# Sheet1.net
KiCad netlist of a schematic drawn in Altium Designer
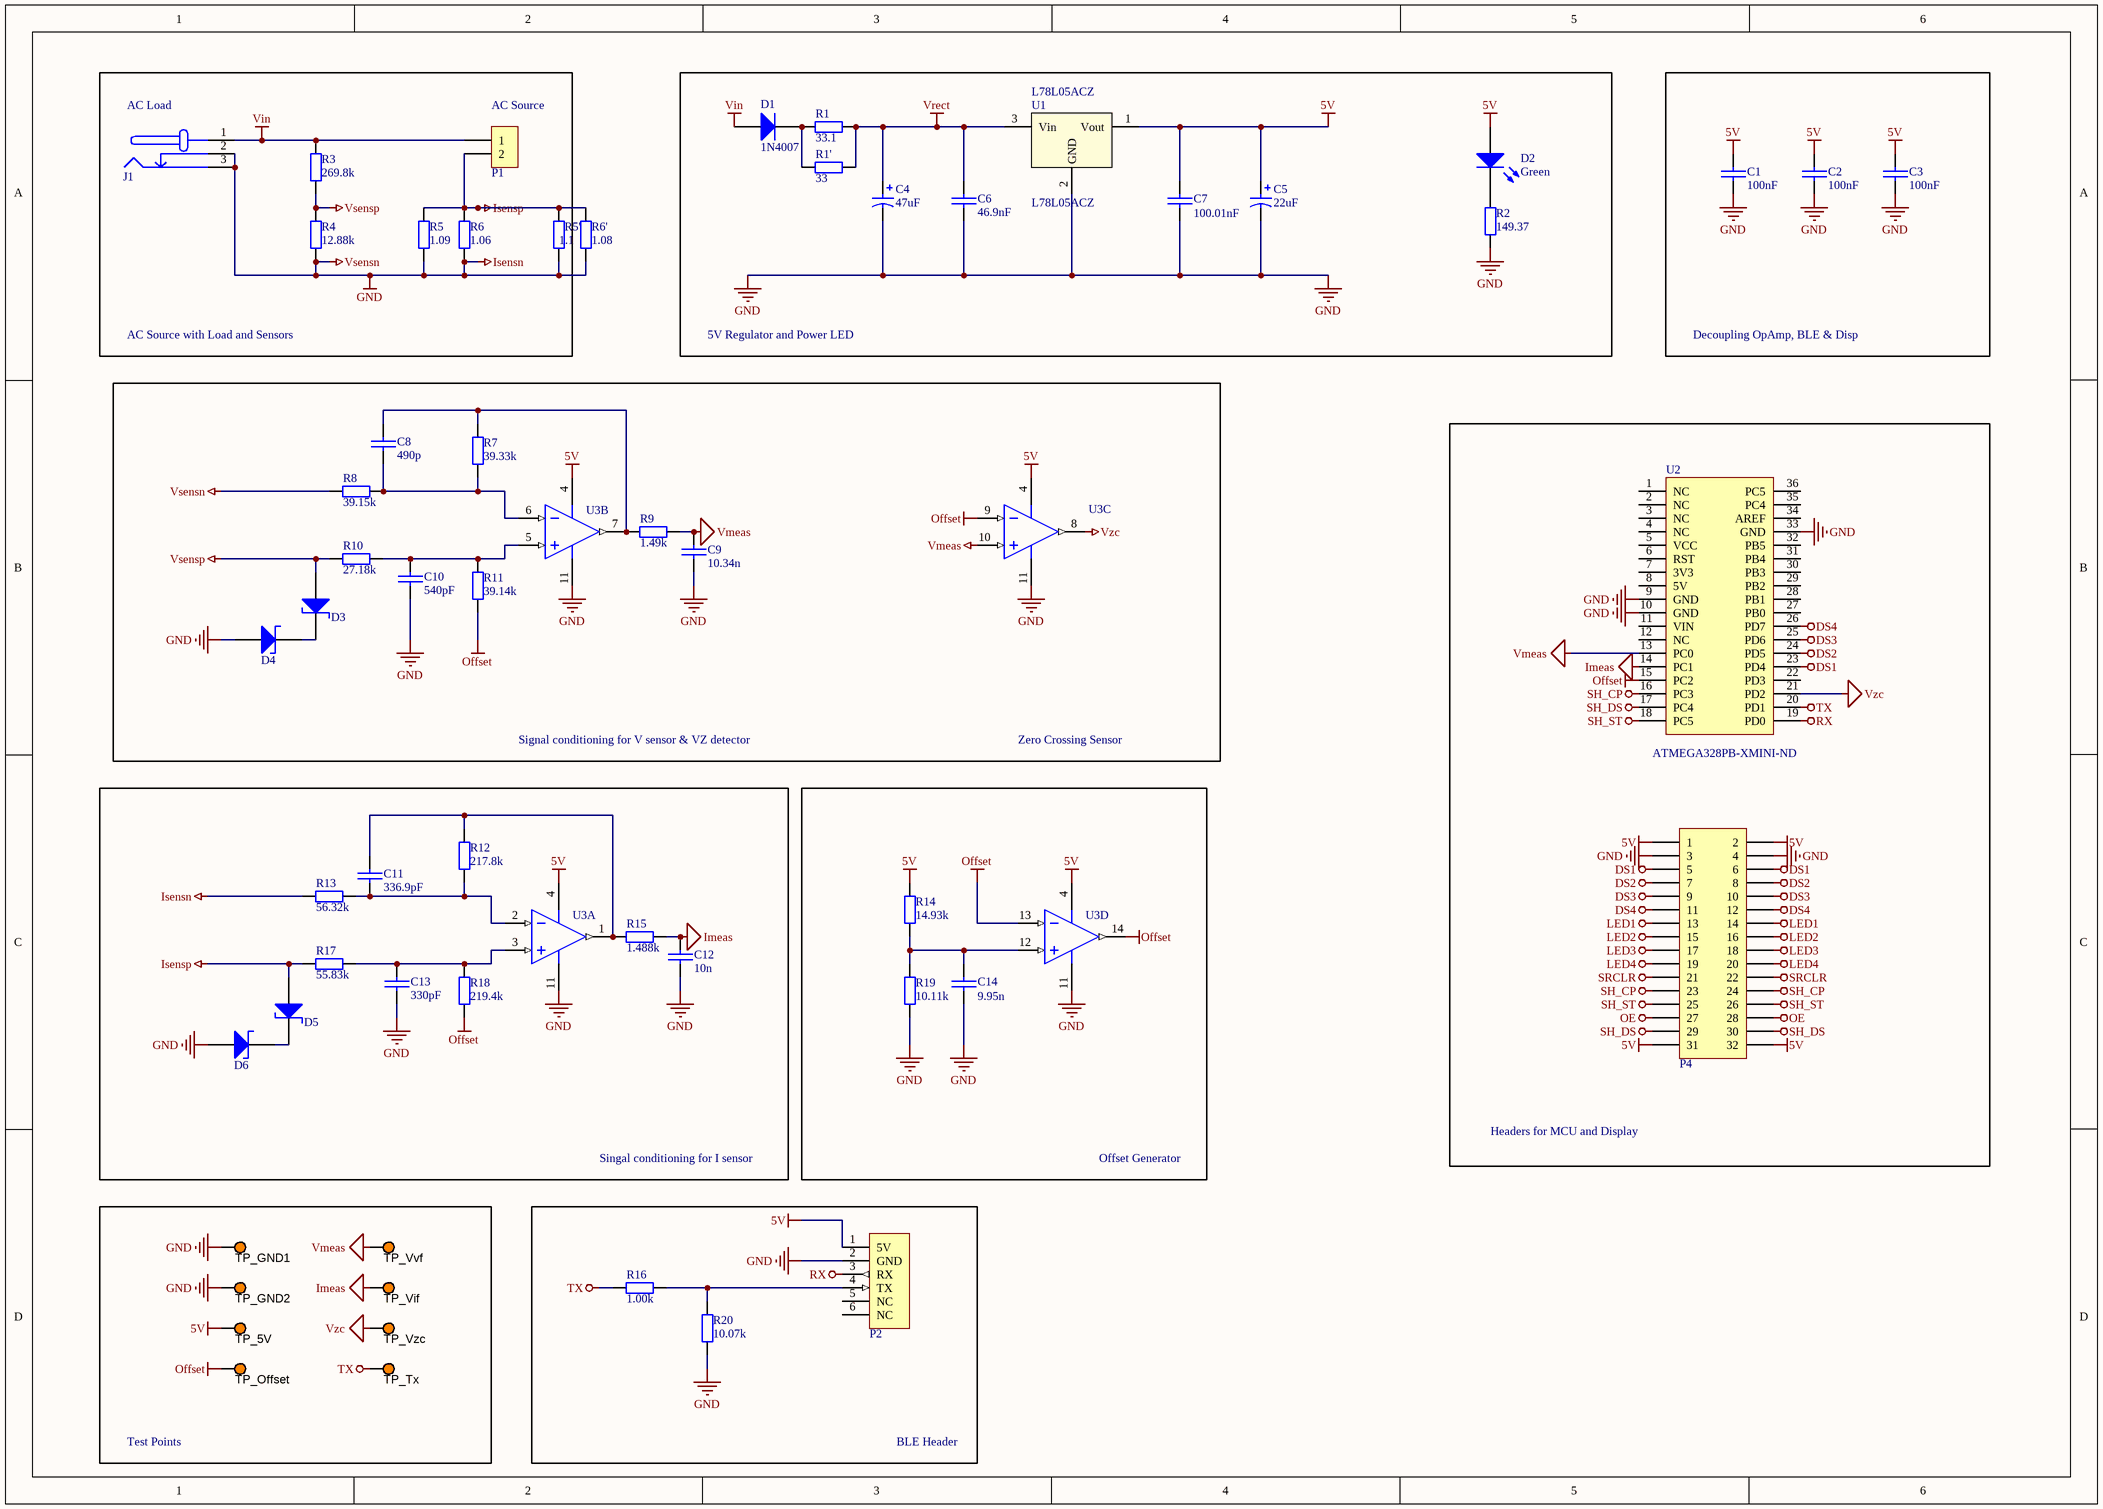
[diagram p0: Sheet1.SchDoc]

(export (version "E")
  (design (tool "Eeschema 10.0.6"))
  (components
    (comp (ref "C1")
      (value "100nF")
      (footprint "CCAP-5P0")
      (description "TH ceramic capacitor with 5mm pitch")
      (libsource (lib "EE209_Library") (part "CerCap_TH_5P0"))
    )
    (comp (ref "C2")
      (value "100nF")
      (footprint "CCAP-5P0")
      (description "TH ceramic capacitor with 5mm pitch")
      (libsource (lib "EE209_Library") (part "CerCap_TH_5P0"))
    )
    (comp (ref "C3")
      (value "100nF")
      (footprint "CCAP-5P0")
      (description "TH ceramic capacitor with 5mm pitch")
      (libsource (lib "EE209_Library") (part "CerCap_TH_5P0"))
    )
    (comp (ref "C4")
      (value "47uF")
      (footprint "CAP-RAD-2.5mm Pitch")
      (description "Electrolytic capacitor with radial package, 2mm pitch and 5.2mm diameter")
      (fields (field (name "PUBLISHER") "Altium Limited"))
      (libsource (lib "EE209_Library") (part "ElecCap_TH_2P0"))
    )
    (comp (ref "C5")
      (value "22uF")
      (footprint "CAP-RAD-2.5mm Pitch")
      (description "Electrolytic capacitor with radial package, 2mm pitch and 5.2mm diameter")
      (fields (field (name "PUBLISHER") "Altium Limited"))
      (libsource (lib "EE209_Library") (part "ElecCap_TH_2P0"))
    )
    (comp (ref "C6")
      (value "46.9nF")
      (footprint "CCAP-5P0")
      (description "TH ceramic capacitor with 5mm pitch")
      (libsource (lib "EE209_Library") (part "CerCap_TH_5P0"))
    )
    (comp (ref "C7")
      (value "100.01nF")
      (footprint "CCAP-5P0")
      (description "TH ceramic capacitor with 5mm pitch")
      (libsource (lib "EE209_Library") (part "CerCap_TH_5P0"))
    )
    (comp (ref "C8")
      (value "490p")
      (footprint "CCAP-5P0")
      (description "TH ceramic capacitor with 5mm pitch")
      (libsource (lib "EE209_Library") (part "CerCap_TH_5P0"))
    )
    (comp (ref "C9")
      (value "10.34n")
      (footprint "CCAP-5P0")
      (description "TH ceramic capacitor with 5mm pitch")
      (libsource (lib "EE209_Library") (part "CerCap_TH_5P0"))
    )
    (comp (ref "C10")
      (value "540pF")
      (footprint "CCAP-5P0")
      (description "TH ceramic capacitor with 5mm pitch")
      (libsource (lib "EE209_Library") (part "CerCap_TH_5P0"))
    )
    (comp (ref "C11")
      (value "336.9pF")
      (footprint "CCAP-5P0")
      (description "TH ceramic capacitor with 5mm pitch")
      (libsource (lib "EE209_Library") (part "CerCap_TH_5P0"))
    )
    (comp (ref "C12")
      (value "10n")
      (footprint "CCAP-5P0")
      (description "TH ceramic capacitor with 5mm pitch")
      (libsource (lib "EE209_Library") (part "CerCap_TH_5P0"))
    )
    (comp (ref "C13")
      (value "330pF")
      (footprint "CCAP-5P0")
      (description "TH ceramic capacitor with 5mm pitch")
      (libsource (lib "EE209_Library") (part "CerCap_TH_5P0"))
    )
    (comp (ref "C14")
      (value "9.95n")
      (footprint "CCAP-5P0")
      (description "TH ceramic capacitor with 5mm pitch")
      (libsource (lib "EE209_Library") (part "CerCap_TH_5P0"))
    )
    (comp (ref "D1")
      (value "1N4007")
      (footprint "1N4007-MFG")
      (description "1N4007 1000V standard axial diode")
      (libsource (lib "EE209_Library") (part "1N4007_TH_4AX0"))
    )
    (comp (ref "D2")
      (value "Green")
      (footprint "LED")
      (description "Typical throughole GaAs LED with 2.54mm pitch")
      (fields (field (name "MANUFACTURER") "Generic Components") (field (name "PUBLISHER") "Altium Limited"))
      (libsource (lib "EE209_Library") (part "LED_TH_2P54"))
    )
    (comp (ref "D3")
      (value "BZX79-CXVX")
      (footprint "AXIAL-Zener-0.4")
      (description "Axial zener diode BZX79 series")
      (fields
        (field (name "MANUFACTURER") "Nexperia USA Inc.")
        (field (name "MANUFACTURER PART NUMBER") "BZX79-C4V7,143")
      )
      (libsource (lib "EE209_Library") (part "Zener_TH_4AX0"))
    )
    (comp (ref "D4")
      (value "BZX79-CXVX")
      (footprint "AXIAL-Zener-0.4")
      (description "Axial zener diode BZX79 series")
      (fields
        (field (name "MANUFACTURER") "Nexperia USA Inc.")
        (field (name "MANUFACTURER PART NUMBER") "BZX79-C4V7,143")
      )
      (libsource (lib "EE209_Library") (part "Zener_TH_4AX0"))
    )
    (comp (ref "D5")
      (value "BZX79-CXVX")
      (footprint "AXIAL-Zener-0.4")
      (description "Axial zener diode BZX79 series")
      (fields
        (field (name "MANUFACTURER") "Nexperia USA Inc.")
        (field (name "MANUFACTURER PART NUMBER") "BZX79-C4V7,143")
      )
      (libsource (lib "EE209_Library") (part "Zener_TH_4AX0"))
    )
    (comp (ref "D6")
      (value "BZX79-CXVX")
      (footprint "AXIAL-Zener-0.4")
      (description "Axial zener diode BZX79 series")
      (fields
        (field (name "MANUFACTURER") "Nexperia USA Inc.")
        (field (name "MANUFACTURER PART NUMBER") "BZX79-C4V7,143")
      )
      (libsource (lib "EE209_Library") (part "Zener_TH_4AX0"))
    )
    (comp (ref "J1")
      (value "DC barrel jack")
      (footprint "AC-Socket")
      (description "DC barrel jack connection to AC source")
      (libsource (lib "EE209_Library") (part "AC_Input"))
    )
    (comp (ref "P1")
      (value "Dual Banana Plugs")
      (footprint "Dual Banana Plug")
      (description "Dual banana plugs connection to the AC load")
      (fields (field (name "PUBLISHER") "Altium Limited"))
      (libsource (lib "EE209_Library") (part "AC_Output"))
    )
    (comp (ref "P2")
      (value "BLE Module Header")
      (footprint "HM10_HDR1X6")
      (description "2.54mm pitch 6-pin header for BLE module")
      (fields (field (name "PUBLISHER") "Altium Limited"))
      (libsource (lib "EE209_Library") (part "BLEModule_TH"))
    )
    (comp (ref "P4")
      (value "Display")
      (footprint "Display")
      (description "16-Pin Header Connecting Display")
      (libsource (lib "EE209_Library") (part "Display"))
    )
    (comp (ref "R1")
      (value "33.1")
      (footprint "AXIAL-0.4")
      (description "Through hole resistor")
      (fields (field (name "PUBLISHER") "Altium Limited"))
      (libsource (lib "EE209_Library") (part "Res_TH_0AX4"))
    )
    (comp (ref "R1'")
      (value "33")
      (footprint "AXIAL-0.4")
      (description "Through hole resistor")
      (fields (field (name "PUBLISHER") "Altium Limited"))
      (libsource (lib "EE209_Library") (part "Res_TH_0AX4"))
    )
    (comp (ref "R2")
      (value "149.37")
      (footprint "AXIAL-0.4")
      (description "Through hole resistor")
      (fields (field (name "PUBLISHER") "Altium Limited"))
      (libsource (lib "") (part "Res_TH_0AX4_1"))
    )
    (comp (ref "R3")
      (value "269.8k")
      (footprint "AXIAL-0.4")
      (description "Through hole resistor")
      (fields (field (name "PUBLISHER") "Altium Limited"))
      (libsource (lib "") (part "Res_TH_0AX4_2"))
    )
    (comp (ref "R4")
      (value "12.88k")
      (footprint "AXIAL-0.4")
      (description "Through hole resistor")
      (fields (field (name "PUBLISHER") "Altium Limited"))
      (libsource (lib "") (part "Res_TH_0AX4_2"))
    )
    (comp (ref "R5")
      (value "1.09")
      (footprint "AXIAL-0.4")
      (description "Through hole resistor")
      (fields (field (name "PUBLISHER") "Altium Limited"))
      (libsource (lib "") (part "Res_TH_0AX4_2"))
    )
    (comp (ref "R5'")
      (value "1.1")
      (footprint "AXIAL-0.4")
      (description "Through hole resistor")
      (fields (field (name "PUBLISHER") "Altium Limited"))
      (libsource (lib "") (part "Res_TH_0AX4_2"))
    )
    (comp (ref "R6")
      (value "1.06")
      (footprint "AXIAL-0.4")
      (description "Through hole resistor")
      (fields (field (name "PUBLISHER") "Altium Limited"))
      (libsource (lib "") (part "Res_TH_0AX4_2"))
    )
    (comp (ref "R6'")
      (value "1.08")
      (footprint "AXIAL-0.4")
      (description "Through hole resistor")
      (fields (field (name "PUBLISHER") "Altium Limited"))
      (libsource (lib "") (part "Res_TH_0AX4_2"))
    )
    (comp (ref "R7")
      (value "39.33k")
      (footprint "AXIAL-0.4")
      (description "Through hole resistor")
      (fields (field (name "PUBLISHER") "Altium Limited"))
      (libsource (lib "") (part "Res_TH_0AX4_1"))
    )
    (comp (ref "R8")
      (value "39.15k")
      (footprint "AXIAL-0.4")
      (description "Through hole resistor")
      (fields (field (name "PUBLISHER") "Altium Limited"))
      (libsource (lib "EE209_Library") (part "Res_TH_0AX4"))
    )
    (comp (ref "R9")
      (value "1.49k")
      (footprint "AXIAL-0.4")
      (description "Through hole resistor")
      (fields (field (name "PUBLISHER") "Altium Limited"))
      (libsource (lib "EE209_Library") (part "Res_TH_0AX4"))
    )
    (comp (ref "R10")
      (value "27.18k")
      (footprint "AXIAL-0.4")
      (description "Through hole resistor")
      (fields (field (name "PUBLISHER") "Altium Limited"))
      (libsource (lib "EE209_Library") (part "Res_TH_0AX4"))
    )
    (comp (ref "R11")
      (value "39.14k")
      (footprint "AXIAL-0.4")
      (description "Through hole resistor")
      (fields (field (name "PUBLISHER") "Altium Limited"))
      (libsource (lib "") (part "Res_TH_0AX4_1"))
    )
    (comp (ref "R12")
      (value "217.8k")
      (footprint "AXIAL-0.4")
      (description "Through hole resistor")
      (fields (field (name "PUBLISHER") "Altium Limited"))
      (libsource (lib "") (part "Res_TH_0AX4_1"))
    )
    (comp (ref "R13")
      (value "56.32k")
      (footprint "AXIAL-0.4")
      (description "Through hole resistor")
      (fields (field (name "PUBLISHER") "Altium Limited"))
      (libsource (lib "EE209_Library") (part "Res_TH_0AX4"))
    )
    (comp (ref "R14")
      (value "14.93k")
      (footprint "AXIAL-0.4")
      (description "Through hole resistor")
      (fields (field (name "PUBLISHER") "Altium Limited"))
      (libsource (lib "") (part "Res_TH_0AX4_1"))
    )
    (comp (ref "R15")
      (value "1.488k")
      (footprint "AXIAL-0.4")
      (description "Through hole resistor")
      (fields (field (name "PUBLISHER") "Altium Limited"))
      (libsource (lib "EE209_Library") (part "Res_TH_0AX4"))
    )
    (comp (ref "R16")
      (value "1.00k")
      (footprint "AXIAL-0.4")
      (description "Through hole resistor")
      (fields (field (name "PUBLISHER") "Altium Limited"))
      (libsource (lib "EE209_Library") (part "Res_TH_0AX4"))
    )
    (comp (ref "R17")
      (value "55.83k")
      (footprint "AXIAL-0.4")
      (description "Through hole resistor")
      (fields (field (name "PUBLISHER") "Altium Limited"))
      (libsource (lib "EE209_Library") (part "Res_TH_0AX4"))
    )
    (comp (ref "R18")
      (value "219.4k")
      (footprint "AXIAL-0.4")
      (description "Through hole resistor")
      (fields (field (name "PUBLISHER") "Altium Limited"))
      (libsource (lib "") (part "Res_TH_0AX4_1"))
    )
    (comp (ref "R19")
      (value "10.11k")
      (footprint "AXIAL-0.4")
      (description "Through hole resistor")
      (fields (field (name "PUBLISHER") "Altium Limited"))
      (libsource (lib "") (part "Res_TH_0AX4_1"))
    )
    (comp (ref "R20")
      (value "10.07k")
      (footprint "AXIAL-0.4")
      (description "Through hole resistor")
      (fields (field (name "PUBLISHER") "Altium Limited"))
      (libsource (lib "") (part "Res_TH_0AX4_1"))
    )
    (comp (ref "TP_5V")
      (value "5003")
      (footprint "TP_TH")
      (description "Test Point, Orange, 1-Pin THD, RoHS")
      (libsource (lib "EE209_Library") (part "TestPoint"))
    )
    (comp (ref "TP_GND1")
      (value "5003")
      (footprint "TP_TH")
      (description "Test Point, Orange, 1-Pin THD, RoHS")
      (libsource (lib "EE209_Library") (part "TestPoint"))
    )
    (comp (ref "TP_GND2")
      (value "5003")
      (footprint "TP_TH")
      (description "Test Point, Orange, 1-Pin THD, RoHS")
      (libsource (lib "EE209_Library") (part "TestPoint"))
    )
    (comp (ref "TP_Offset")
      (value "5003")
      (footprint "TP_TH")
      (description "Test Point, Orange, 1-Pin THD, RoHS")
      (libsource (lib "EE209_Library") (part "TestPoint"))
    )
    (comp (ref "TP_Tx")
      (value "5003")
      (footprint "TP_TH")
      (description "Test Point, Orange, 1-Pin THD, RoHS")
      (libsource (lib "EE209_Library") (part "TestPoint"))
    )
    (comp (ref "TP_Vif")
      (value "5003")
      (footprint "TP_TH")
      (description "Test Point, Orange, 1-Pin THD, RoHS")
      (libsource (lib "EE209_Library") (part "TestPoint"))
    )
    (comp (ref "TP_Vvf")
      (value "5003")
      (footprint "TP_TH")
      (description "Test Point, Orange, 1-Pin THD, RoHS")
      (libsource (lib "EE209_Library") (part "TestPoint"))
    )
    (comp (ref "TP_Vzc")
      (value "5003")
      (footprint "TP_TH")
      (description "Test Point, Orange, 1-Pin THD, RoHS")
      (libsource (lib "EE209_Library") (part "TestPoint"))
    )
    (comp (ref "U1")
      (value "L78L05ACZ")
      (footprint "TO-92")
      (description "Voltage Regulator 5V")
      (fields
        (field (name "MANUFACTURER") "ON Semiconductor")
        (field (name "MANUFACTURER PART NUMBER") "LM78L05ACZX")
      )
      (libsource (lib "EE209_Library") (part "L78L05_TH_TO92"))
    )
    (comp (ref "U2")
      (value "ATmega328PB Xplained Mini Header")
      (footprint "ATmeg328P Xplained")
      (description "Dual 18-pin headers connecting to ATmega328PB Xplained Mini")
      (fields
        (field (name "MANUFACTURER") "Microchip Technology")
        (field (name "MANUFACTURER PART NUMBER") "ATMEGA328PB-XMINI")
        (field (name "SUPPLIER PART NUMBER 1") "ATMEGA328PB-XMINI-ND")
      )
      (libsource (lib "EE209_Library") (part "ATmega328PBXplained_TH"))
    )
    (comp (ref "U3")
      (value "LM324")
      (footprint "DIP-14")
      (description "IC OPAMP GP 14DIP")
      (fields
        (field (name "MANUFACTURER") "ON Semiconductor")
        (field (name "MANUFACTURER PART NUMBER") "LM324N")
      )
      (libsource (lib "EE209_Library") (part "LM324N_TH_DIP16"))
    )
  )
  (nets
    (net (code "1") (name "5V") (class "Default")
      (node (ref "C1") (pin "1") (pinfunction "1_1") (pintype "passive"))
      (node (ref "C2") (pin "1") (pinfunction "1_1") (pintype "passive"))
      (node (ref "C3") (pin "1") (pinfunction "1_1") (pintype "passive"))
      (node (ref "C5") (pin "1") (pinfunction "1_1") (pintype "passive"))
      (node (ref "C7") (pin "1") (pinfunction "1_1") (pintype "passive"))
      (node (ref "D2") (pin "1") (pinfunction "A_1") (pintype "passive"))
      (node (ref "P2") (pin "1") (pinfunction "5V_1") (pintype "passive"))
      (node (ref "P4") (pin "1") (pinfunction "1_1") (pintype "passive"))
      (node (ref "P4") (pin "2") (pinfunction "2_2") (pintype "passive"))
      (node (ref "P4") (pin "31") (pinfunction "31_31") (pintype "passive"))
      (node (ref "P4") (pin "32") (pinfunction "32_32") (pintype "passive"))
      (node (ref "R14") (pin "1") (pinfunction "1_1") (pintype "passive"))
      (node (ref "TP_5V") (pin "1") (pinfunction "1_1") (pintype "passive"))
      (node (ref "U1") (pin "1") (pinfunction "Vout_1") (pintype "passive"))
      (node (ref "U3") (pin "4") (pinfunction "VDD_4") (pintype "power_in"))
    )
    (net (code "2") (name "DS1") (class "Default")
      (node (ref "P4") (pin "5") (pinfunction "5_5") (pintype "passive"))
      (node (ref "P4") (pin "6") (pinfunction "6_6") (pintype "passive"))
      (node (ref "U2") (pin "23") (pinfunction "PD4_23") (pintype "passive"))
    )
    (net (code "3") (name "DS2") (class "Default")
      (node (ref "P4") (pin "7") (pinfunction "7_7") (pintype "passive"))
      (node (ref "P4") (pin "8") (pinfunction "8_8") (pintype "passive"))
      (node (ref "U2") (pin "24") (pinfunction "PD5_24") (pintype "passive"))
    )
    (net (code "4") (name "DS3") (class "Default")
      (node (ref "P4") (pin "10") (pinfunction "10_10") (pintype "passive"))
      (node (ref "P4") (pin "9") (pinfunction "9_9") (pintype "passive"))
      (node (ref "U2") (pin "25") (pinfunction "PD6_25") (pintype "passive"))
    )
    (net (code "5") (name "DS4") (class "Default")
      (node (ref "P4") (pin "11") (pinfunction "11_11") (pintype "passive"))
      (node (ref "P4") (pin "12") (pinfunction "12_12") (pintype "passive"))
      (node (ref "U2") (pin "26") (pinfunction "PD7_26") (pintype "passive"))
    )
    (net (code "6") (name "GND") (class "Default")
      (node (ref "C1") (pin "2") (pinfunction "2_2") (pintype "passive"))
      (node (ref "C10") (pin "2") (pinfunction "2_2") (pintype "passive"))
      (node (ref "C12") (pin "2") (pinfunction "2_2") (pintype "passive"))
      (node (ref "C13") (pin "2") (pinfunction "2_2") (pintype "passive"))
      (node (ref "C14") (pin "2") (pinfunction "2_2") (pintype "passive"))
      (node (ref "C2") (pin "2") (pinfunction "2_2") (pintype "passive"))
      (node (ref "C3") (pin "2") (pinfunction "2_2") (pintype "passive"))
      (node (ref "C4") (pin "2") (pinfunction "2_2") (pintype "passive"))
      (node (ref "C5") (pin "2") (pinfunction "2_2") (pintype "passive"))
      (node (ref "C6") (pin "2") (pinfunction "2_2") (pintype "passive"))
      (node (ref "C7") (pin "2") (pinfunction "2_2") (pintype "passive"))
      (node (ref "C9") (pin "2") (pinfunction "2_2") (pintype "passive"))
      (node (ref "D4") (pin "1") (pinfunction "A_1") (pintype "passive"))
      (node (ref "D6") (pin "1") (pinfunction "A_1") (pintype "passive"))
      (node (ref "J1") (pin "2") (pinfunction "GND_ALT_2") (pintype "power_in"))
      (node (ref "J1") (pin "3") (pinfunction "GND_3") (pintype "power_in"))
      (node (ref "P2") (pin "2") (pinfunction "GND_2") (pintype "passive"))
      (node (ref "P4") (pin "3") (pinfunction "3_3") (pintype "passive"))
      (node (ref "P4") (pin "4") (pinfunction "4_4") (pintype "passive"))
      (node (ref "R13") (pin "1") (pinfunction "1_1") (pintype "passive"))
      (node (ref "R19") (pin "2") (pinfunction "2_2") (pintype "passive"))
      (node (ref "R2") (pin "2") (pinfunction "2_2") (pintype "passive"))
      (node (ref "R20") (pin "2") (pinfunction "2_2") (pintype "passive"))
      (node (ref "R4") (pin "1") (pinfunction "1_1") (pintype "passive"))
      (node (ref "R5") (pin "1") (pinfunction "1_1") (pintype "passive"))
      (node (ref "R5'") (pin "1") (pinfunction "1_1") (pintype "passive"))
      (node (ref "R6") (pin "1") (pinfunction "1_1") (pintype "passive"))
      (node (ref "R6'") (pin "1") (pinfunction "1_1") (pintype "passive"))
      (node (ref "R8") (pin "1") (pinfunction "1_1") (pintype "passive"))
      (node (ref "TP_GND1") (pin "1") (pinfunction "1_1") (pintype "passive"))
      (node (ref "TP_GND2") (pin "1") (pinfunction "1_1") (pintype "passive"))
      (node (ref "U1") (pin "2") (pinfunction "GND_2") (pintype "passive"))
      (node (ref "U2") (pin "10") (pinfunction "GND_10") (pintype "power_in"))
      (node (ref "U2") (pin "33") (pinfunction "GND_33") (pintype "passive"))
      (node (ref "U2") (pin "9") (pinfunction "GND_9") (pintype "power_in"))
      (node (ref "U3") (pin "11") (pinfunction "VSS_11") (pintype "power_in"))
    )
    (net (code "7") (name "Imeas") (class "Default")
      (node (ref "C12") (pin "1") (pinfunction "1_1") (pintype "passive"))
      (node (ref "R15") (pin "2") (pinfunction "2_2") (pintype "passive"))
      (node (ref "TP_Vif") (pin "1") (pinfunction "1_1") (pintype "passive"))
      (node (ref "U2") (pin "14") (pinfunction "PC1_14") (pintype "passive"))
    )
    (net (code "8") (name "Isensp") (class "Default")
      (node (ref "D5") (pin "1") (pinfunction "A_1") (pintype "passive"))
      (node (ref "P1") (pin "2") (pinfunction "2_2") (pintype "passive"))
      (node (ref "R17") (pin "1") (pinfunction "1_1") (pintype "passive"))
      (node (ref "R5") (pin "2") (pinfunction "2_2") (pintype "passive"))
      (node (ref "R5'") (pin "2") (pinfunction "2_2") (pintype "passive"))
      (node (ref "R6") (pin "2") (pinfunction "2_2") (pintype "passive"))
      (node (ref "R6'") (pin "2") (pinfunction "2_2") (pintype "passive"))
    )
    (net (code "9") (name "LED1") (class "Default")
      (node (ref "P4") (pin "13") (pinfunction "13_13") (pintype "passive"))
      (node (ref "P4") (pin "14") (pinfunction "14_14") (pintype "passive"))
    )
    (net (code "10") (name "LED2") (class "Default")
      (node (ref "P4") (pin "15") (pinfunction "15_15") (pintype "passive"))
      (node (ref "P4") (pin "16") (pinfunction "16_16") (pintype "passive"))
    )
    (net (code "11") (name "LED3") (class "Default")
      (node (ref "P4") (pin "17") (pinfunction "17_17") (pintype "passive"))
      (node (ref "P4") (pin "18") (pinfunction "18_18") (pintype "passive"))
    )
    (net (code "12") (name "LED4") (class "Default")
      (node (ref "P4") (pin "19") (pinfunction "19_19") (pintype "passive"))
      (node (ref "P4") (pin "20") (pinfunction "20_20") (pintype "passive"))
    )
    (net (code "13") (name "Net-(D1-K)") (class "Default")
      (node (ref "D1") (pin "2") (pinfunction "K_2") (pintype "passive"))
      (node (ref "R1") (pin "1") (pinfunction "1_1") (pintype "passive"))
      (node (ref "R1'") (pin "1") (pinfunction "1_1") (pintype "passive"))
    )
    (net (code "14") (name "Net-(D2-K)") (class "Default")
      (node (ref "D2") (pin "2") (pinfunction "K_2") (pintype "passive"))
      (node (ref "R2") (pin "1") (pinfunction "1_1") (pintype "passive"))
    )
    (net (code "15") (name "Net-(D3-K)") (class "Default")
      (node (ref "D3") (pin "2") (pinfunction "K_2") (pintype "passive"))
      (node (ref "D4") (pin "2") (pinfunction "K_2") (pintype "passive"))
    )
    (net (code "16") (name "Net-(D5-K)") (class "Default")
      (node (ref "D5") (pin "2") (pinfunction "K_2") (pintype "passive"))
      (node (ref "D6") (pin "2") (pinfunction "K_2") (pintype "passive"))
    )
    (net (code "17") (name "Net-(P2-TX)") (class "Default")
      (node (ref "P2") (pin "4") (pinfunction "TX_4") (pintype "input"))
      (node (ref "R16") (pin "2") (pinfunction "2_2") (pintype "passive"))
      (node (ref "R20") (pin "1") (pinfunction "1_1") (pintype "passive"))
    )
    (net (code "18") (name "Net-(U3A-VINA+)") (class "Default")
      (node (ref "C13") (pin "1") (pinfunction "1_1") (pintype "passive"))
      (node (ref "R17") (pin "2") (pinfunction "2_2") (pintype "passive"))
      (node (ref "R18") (pin "1") (pinfunction "1_1") (pintype "passive"))
      (node (ref "U3") (pin "3") (pinfunction "VINA+_3") (pintype "input"))
    )
    (net (code "19") (name "Net-(U3A-VINA-)") (class "Default")
      (node (ref "C11") (pin "2") (pinfunction "2_2") (pintype "passive"))
      (node (ref "R12") (pin "2") (pinfunction "2_2") (pintype "passive"))
      (node (ref "R13") (pin "2") (pinfunction "2_2") (pintype "passive"))
      (node (ref "U3") (pin "2") (pinfunction "VINA-_2") (pintype "input"))
    )
    (net (code "20") (name "Net-(U3A-VOUTA)") (class "Default")
      (node (ref "C11") (pin "1") (pinfunction "1_1") (pintype "passive"))
      (node (ref "R12") (pin "1") (pinfunction "1_1") (pintype "passive"))
      (node (ref "R15") (pin "1") (pinfunction "1_1") (pintype "passive"))
      (node (ref "U3") (pin "1") (pinfunction "VOUTA_1") (pintype "output"))
    )
    (net (code "21") (name "Net-(U3B-VINB+)") (class "Default")
      (node (ref "C10") (pin "1") (pinfunction "1_1") (pintype "passive"))
      (node (ref "R10") (pin "2") (pinfunction "2_2") (pintype "passive"))
      (node (ref "R11") (pin "1") (pinfunction "1_1") (pintype "passive"))
      (node (ref "U3") (pin "5") (pinfunction "VINB+_5") (pintype "input"))
    )
    (net (code "22") (name "Net-(U3B-VINB-)") (class "Default")
      (node (ref "C8") (pin "2") (pinfunction "2_2") (pintype "passive"))
      (node (ref "R7") (pin "2") (pinfunction "2_2") (pintype "passive"))
      (node (ref "R8") (pin "2") (pinfunction "2_2") (pintype "passive"))
      (node (ref "U3") (pin "6") (pinfunction "VINB-_6") (pintype "input"))
    )
    (net (code "23") (name "Net-(U3B-VOUTB)") (class "Default")
      (node (ref "C8") (pin "1") (pinfunction "1_1") (pintype "passive"))
      (node (ref "R7") (pin "1") (pinfunction "1_1") (pintype "passive"))
      (node (ref "R9") (pin "1") (pinfunction "1_1") (pintype "passive"))
      (node (ref "U3") (pin "7") (pinfunction "VOUTB_7") (pintype "output"))
    )
    (net (code "24") (name "Net-(U3D-VIND+)") (class "Default")
      (node (ref "C14") (pin "1") (pinfunction "1_1") (pintype "passive"))
      (node (ref "R14") (pin "2") (pinfunction "2_2") (pintype "passive"))
      (node (ref "R19") (pin "1") (pinfunction "1_1") (pintype "passive"))
      (node (ref "U3") (pin "12") (pinfunction "VIND+_12") (pintype "input"))
    )
    (net (code "25") (name "OE") (class "Default")
      (node (ref "P4") (pin "27") (pinfunction "27_27") (pintype "passive"))
      (node (ref "P4") (pin "28") (pinfunction "28_28") (pintype "passive"))
    )
    (net (code "26") (name "Offset") (class "Default")
      (node (ref "R11") (pin "2") (pinfunction "2_2") (pintype "passive"))
      (node (ref "R18") (pin "2") (pinfunction "2_2") (pintype "passive"))
      (node (ref "TP_Offset") (pin "1") (pinfunction "1_1") (pintype "passive"))
      (node (ref "U2") (pin "15") (pinfunction "PC2_15") (pintype "passive"))
      (node (ref "U3") (pin "13") (pinfunction "VIND-_13") (pintype "input"))
      (node (ref "U3") (pin "14") (pinfunction "VOUTD_14") (pintype "output"))
      (node (ref "U3") (pin "9") (pinfunction "VINC-_9") (pintype "input"))
    )
    (net (code "27") (name "RX") (class "Default")
      (node (ref "P2") (pin "3") (pinfunction "RX_3") (pintype "output"))
      (node (ref "U2") (pin "19") (pinfunction "PD0_19") (pintype "passive"))
    )
    (net (code "28") (name "SH_CP") (class "Default")
      (node (ref "P4") (pin "23") (pinfunction "23_23") (pintype "passive"))
      (node (ref "P4") (pin "24") (pinfunction "24_24") (pintype "passive"))
      (node (ref "U2") (pin "16") (pinfunction "PC3_16") (pintype "passive"))
    )
    (net (code "29") (name "SH_DS") (class "Default")
      (node (ref "P4") (pin "29") (pinfunction "29_29") (pintype "passive"))
      (node (ref "P4") (pin "30") (pinfunction "30_30") (pintype "passive"))
      (node (ref "U2") (pin "17") (pinfunction "PC4_17") (pintype "passive"))
    )
    (net (code "30") (name "SH_ST") (class "Default")
      (node (ref "P4") (pin "25") (pinfunction "25_25") (pintype "passive"))
      (node (ref "P4") (pin "26") (pinfunction "26_26") (pintype "passive"))
      (node (ref "U2") (pin "18") (pinfunction "PC5_18") (pintype "passive"))
    )
    (net (code "31") (name "SRCLR") (class "Default")
      (node (ref "P4") (pin "21") (pinfunction "21_21") (pintype "passive"))
      (node (ref "P4") (pin "22") (pinfunction "22_22") (pintype "passive"))
    )
    (net (code "32") (name "TX") (class "Default")
      (node (ref "R16") (pin "1") (pinfunction "1_1") (pintype "passive"))
      (node (ref "TP_Tx") (pin "1") (pinfunction "1_1") (pintype "passive"))
      (node (ref "U2") (pin "20") (pinfunction "PD1_20") (pintype "passive"))
    )
    (net (code "33") (name "Vin") (class "Default")
      (node (ref "D1") (pin "1") (pinfunction "A_1") (pintype "passive"))
      (node (ref "J1") (pin "1") (pinfunction "VCC_1") (pintype "power_in"))
      (node (ref "P1") (pin "1") (pinfunction "1_1") (pintype "passive"))
      (node (ref "R3") (pin "2") (pinfunction "2_2") (pintype "passive"))
    )
    (net (code "34") (name "Vmeas") (class "Default")
      (node (ref "C9") (pin "1") (pinfunction "1_1") (pintype "passive"))
      (node (ref "R9") (pin "2") (pinfunction "2_2") (pintype "passive"))
      (node (ref "TP_Vvf") (pin "1") (pinfunction "1_1") (pintype "passive"))
      (node (ref "U2") (pin "13") (pinfunction "PC0_13") (pintype "passive"))
      (node (ref "U3") (pin "10") (pinfunction "VINC+_10") (pintype "input"))
    )
    (net (code "35") (name "Vrect") (class "Default")
      (node (ref "C4") (pin "1") (pinfunction "1_1") (pintype "passive"))
      (node (ref "C6") (pin "1") (pinfunction "1_1") (pintype "passive"))
      (node (ref "R1") (pin "2") (pinfunction "2_2") (pintype "passive"))
      (node (ref "R1'") (pin "2") (pinfunction "2_2") (pintype "passive"))
      (node (ref "U1") (pin "3") (pinfunction "Vin_3") (pintype "passive"))
    )
    (net (code "36") (name "Vsensp") (class "Default")
      (node (ref "D3") (pin "1") (pinfunction "A_1") (pintype "passive"))
      (node (ref "R10") (pin "1") (pinfunction "1_1") (pintype "passive"))
      (node (ref "R3") (pin "1") (pinfunction "1_1") (pintype "passive"))
      (node (ref "R4") (pin "2") (pinfunction "2_2") (pintype "passive"))
    )
    (net (code "37") (name "Vzc") (class "Default")
      (node (ref "TP_Vzc") (pin "1") (pinfunction "1_1") (pintype "passive"))
      (node (ref "U2") (pin "21") (pinfunction "PD2_21") (pintype "passive"))
      (node (ref "U3") (pin "8") (pinfunction "VOUTC_8") (pintype "output"))
    )
    (net (code "38") (name "unconnected-(P2-NC-Pad5)") (class "Default")
      (node (ref "P2") (pin "5") (pinfunction "NC_5") (pintype "passive"))
    )
    (net (code "39") (name "unconnected-(P2-NC-Pad6)") (class "Default")
      (node (ref "P2") (pin "6") (pinfunction "NC_6") (pintype "passive"))
    )
    (net (code "40") (name "unconnected-(U2-3V3-Pad7)") (class "Default")
      (node (ref "U2") (pin "7") (pinfunction "3V3_7") (pintype "passive"))
    )
    (net (code "41") (name "unconnected-(U2-5V-Pad8)") (class "Default")
      (node (ref "U2") (pin "8") (pinfunction "5V_8") (pintype "power_in"))
    )
    (net (code "42") (name "unconnected-(U2-AREF-Pad34)") (class "Default")
      (node (ref "U2") (pin "34") (pinfunction "AREF_34") (pintype "passive"))
    )
    (net (code "43") (name "unconnected-(U2-NC-Pad1)") (class "Default")
      (node (ref "U2") (pin "1") (pinfunction "NC_1") (pintype "passive"))
    )
    (net (code "44") (name "unconnected-(U2-NC-Pad2)") (class "Default")
      (node (ref "U2") (pin "2") (pinfunction "NC_2") (pintype "passive"))
    )
    (net (code "45") (name "unconnected-(U2-NC-Pad3)") (class "Default")
      (node (ref "U2") (pin "3") (pinfunction "NC_3") (pintype "passive"))
    )
    (net (code "46") (name "unconnected-(U2-NC-Pad4)") (class "Default")
      (node (ref "U2") (pin "4") (pinfunction "NC_4") (pintype "passive"))
    )
    (net (code "47") (name "unconnected-(U2-NC-Pad12)") (class "Default")
      (node (ref "U2") (pin "12") (pinfunction "NC_12") (pintype "passive"))
    )
    (net (code "48") (name "unconnected-(U2-PB0-Pad27)") (class "Default")
      (node (ref "U2") (pin "27") (pinfunction "PB0_27") (pintype "passive"))
    )
    (net (code "49") (name "unconnected-(U2-PB1-Pad28)") (class "Default")
      (node (ref "U2") (pin "28") (pinfunction "PB1_28") (pintype "passive"))
    )
    (net (code "50") (name "unconnected-(U2-PB2-Pad29)") (class "Default")
      (node (ref "U2") (pin "29") (pinfunction "PB2_29") (pintype "passive"))
    )
    (net (code "51") (name "unconnected-(U2-PB3-Pad30)") (class "Default")
      (node (ref "U2") (pin "30") (pinfunction "PB3_30") (pintype "passive"))
    )
    (net (code "52") (name "unconnected-(U2-PB4-Pad31)") (class "Default")
      (node (ref "U2") (pin "31") (pinfunction "PB4_31") (pintype "passive"))
    )
    (net (code "53") (name "unconnected-(U2-PB5-Pad32)") (class "Default")
      (node (ref "U2") (pin "32") (pinfunction "PB5_32") (pintype "passive"))
    )
    (net (code "54") (name "unconnected-(U2-PC4-Pad35)") (class "Default")
      (node (ref "U2") (pin "35") (pinfunction "PC4_35") (pintype "passive"))
    )
    (net (code "55") (name "unconnected-(U2-PC5-Pad36)") (class "Default")
      (node (ref "U2") (pin "36") (pinfunction "PC5_36") (pintype "passive"))
    )
    (net (code "56") (name "unconnected-(U2-PD3-Pad22)") (class "Default")
      (node (ref "U2") (pin "22") (pinfunction "PD3_22") (pintype "passive"))
    )
    (net (code "57") (name "unconnected-(U2-RST-Pad6)") (class "Default")
      (node (ref "U2") (pin "6") (pinfunction "RST_6") (pintype "passive"))
    )
    (net (code "58") (name "unconnected-(U2-VCC-Pad5)") (class "Default")
      (node (ref "U2") (pin "5") (pinfunction "VCC_5") (pintype "power_in"))
    )
    (net (code "59") (name "unconnected-(U2-VIN-Pad11)") (class "Default")
      (node (ref "U2") (pin "11") (pinfunction "VIN_11") (pintype "power_in"))
    )
  )
)
